# rapidshark-forward-breakout-mk-1_2.net
KiCad netlist of a schematic drawn in EAGLE
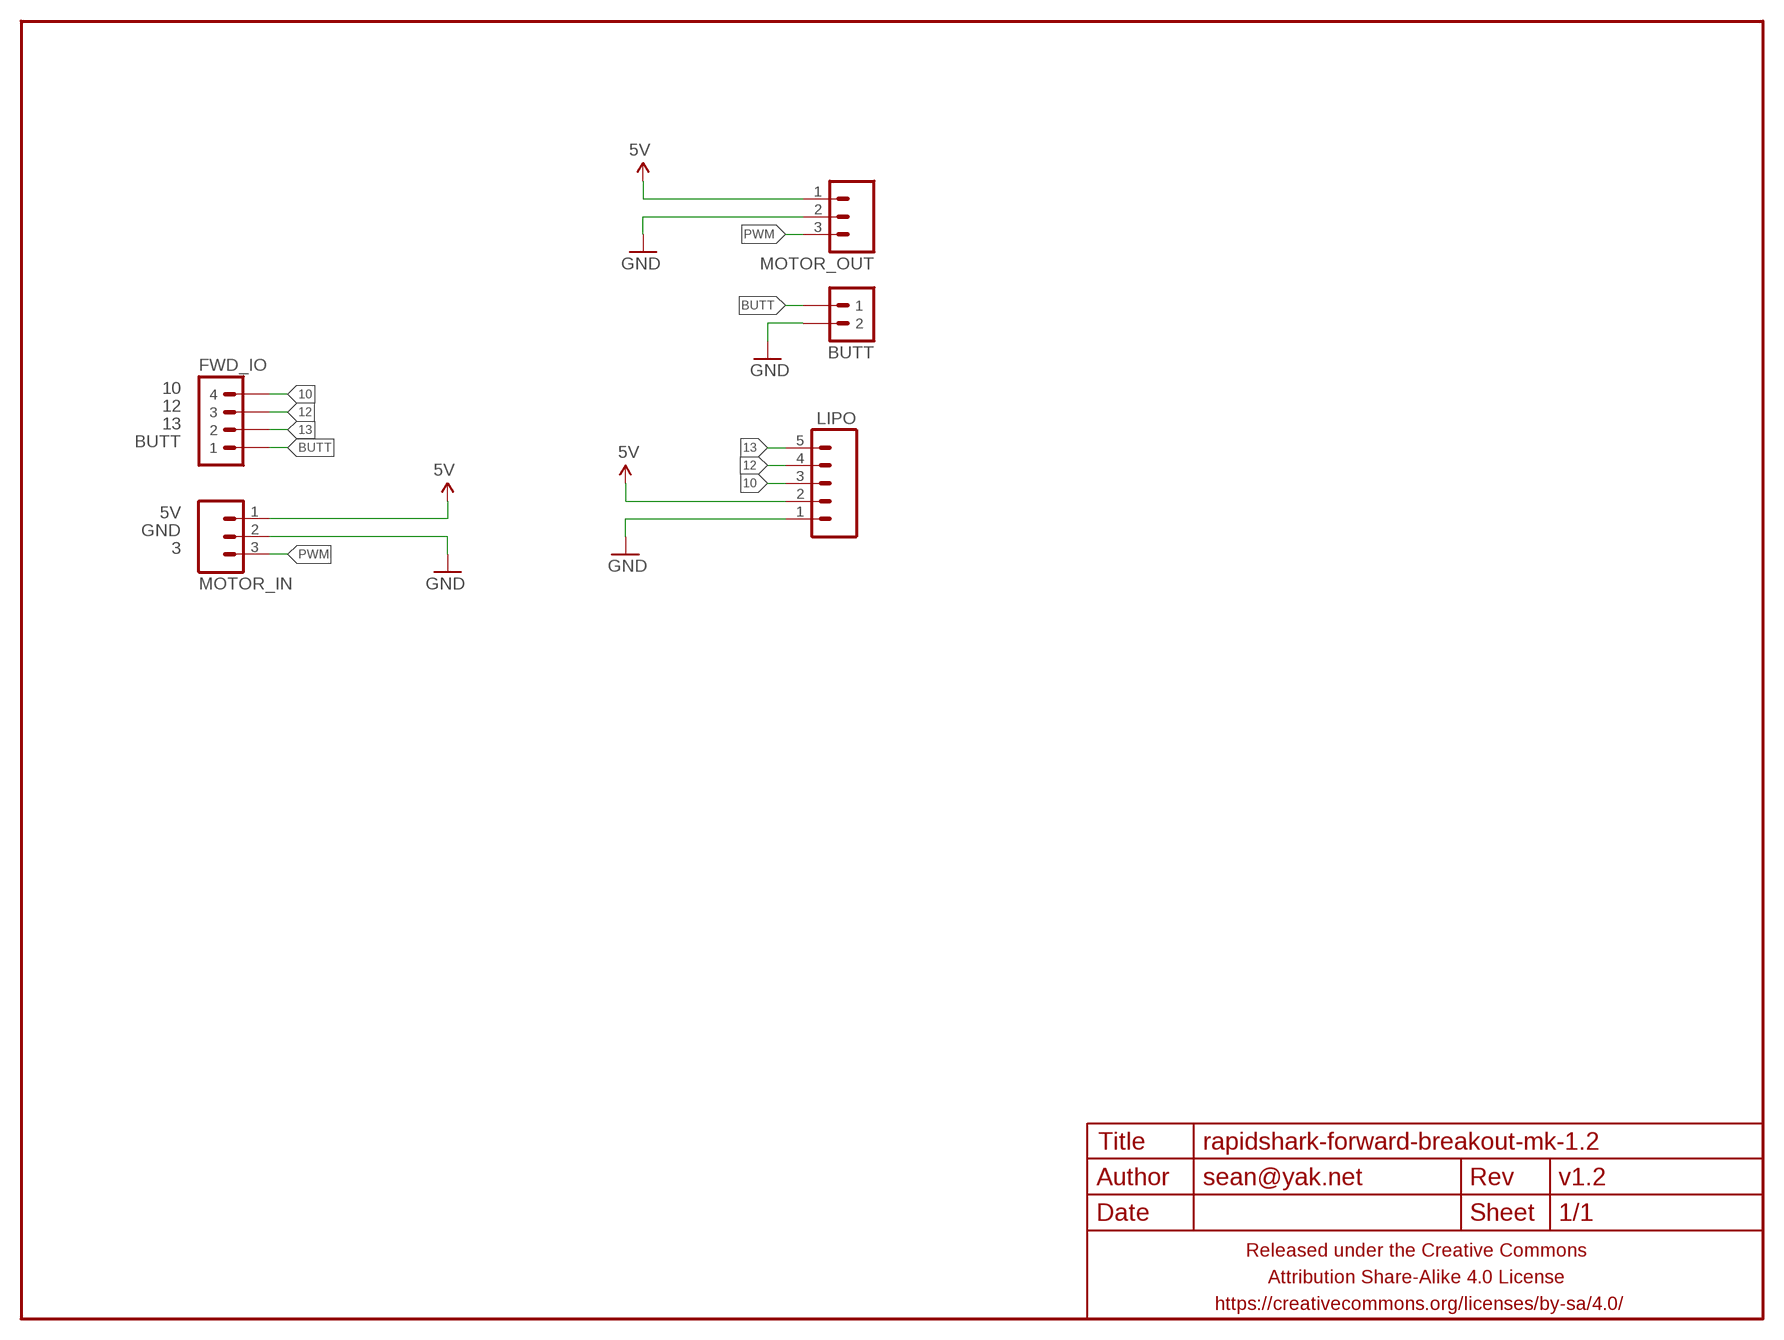
[diagram p0: schematic, sheet 1]

(export (version "E")
  (design (tool "Eeschema 10.0.6"))
  (components
    (comp (ref "BUTT")
      (value "M02JST-PTH-VERT")
      (footprint "eagle-import:JST-2-PH-VERT-PTH")
      (libsource (lib "eagle-import") (part "M02JST-PTH-VERT"))
    )
    (comp (ref "FRAME1")
      (value "FRAME-LETTERNO_PACKAGE")
      (footprint "eagle-import:DUMMY")
      (fields (field (name "DESIGNER") "sean@yak.net") (field (name "VERSION") "v1.2"))
      (libsource (lib "eagle-import") (part "FRAME-LETTERNO_PACKAGE"))
    )
    (comp (ref "FWD_IO")
      (value "M04JST-PTH-VERT")
      (footprint "eagle-import:JST-4-PH-VERT-PTH")
      (libsource (lib "eagle-import") (part "M04JST-PTH-VERT"))
    )
    (comp (ref "LIPO")
      (value "M05JST-PH-VERT-PTH")
      (footprint "eagle-import:JST-5-PH-VERT-PTH")
      (libsource (lib "eagle-import") (part "M05JST-PH-VERT-PTH"))
    )
    (comp (ref "MOTOR_IN")
      (value "M03JST-PTH-VERT")
      (footprint "eagle-import:JST-3-PH-VERT-PTH")
      (libsource (lib "eagle-import") (part "M03JST-PTH-VERT"))
    )
    (comp (ref "MOTOR_OUT")
      (value "M03JST-PTH-VERT")
      (footprint "eagle-import:JST-3-PH-VERT-PTH")
      (libsource (lib "eagle-import") (part "M03JST-PTH-VERT"))
    )
  )
  (nets
    (net (code "1") (name "5V") (class "Default")
      (node (ref "LIPO") (pin "2") (pinfunction "2_2") (pintype "passive"))
      (node (ref "MOTOR_IN") (pin "1") (pinfunction "1_1") (pintype "passive"))
      (node (ref "MOTOR_OUT") (pin "1") (pinfunction "1_1") (pintype "passive"))
    )
    (net (code "2") (name "10") (class "Default")
      (node (ref "FWD_IO") (pin "4") (pinfunction "4_4") (pintype "passive"))
      (node (ref "LIPO") (pin "3") (pinfunction "3_3") (pintype "passive"))
    )
    (net (code "3") (name "12") (class "Default")
      (node (ref "FWD_IO") (pin "3") (pinfunction "3_3") (pintype "passive"))
      (node (ref "LIPO") (pin "4") (pinfunction "4_4") (pintype "passive"))
    )
    (net (code "4") (name "13") (class "Default")
      (node (ref "FWD_IO") (pin "2") (pinfunction "2_2") (pintype "passive"))
      (node (ref "LIPO") (pin "5") (pinfunction "5_5") (pintype "passive"))
    )
    (net (code "5") (name "BUTT") (class "Default")
      (node (ref "BUTT") (pin "1") (pinfunction "1_1") (pintype "passive"))
      (node (ref "FWD_IO") (pin "1") (pinfunction "1_1") (pintype "passive"))
    )
    (net (code "6") (name "GND") (class "Default")
      (node (ref "BUTT") (pin "2") (pinfunction "2_2") (pintype "passive"))
      (node (ref "LIPO") (pin "1") (pinfunction "1_1") (pintype "passive"))
      (node (ref "MOTOR_IN") (pin "2") (pinfunction "2_2") (pintype "passive"))
      (node (ref "MOTOR_OUT") (pin "2") (pinfunction "2_2") (pintype "passive"))
    )
    (net (code "7") (name "PWM") (class "Default")
      (node (ref "MOTOR_IN") (pin "3") (pinfunction "3_3") (pintype "passive"))
      (node (ref "MOTOR_OUT") (pin "3") (pinfunction "3_3") (pintype "passive"))
    )
  )
)
